# wifiboard.net
KiCad netlist of a schematic drawn in EAGLE
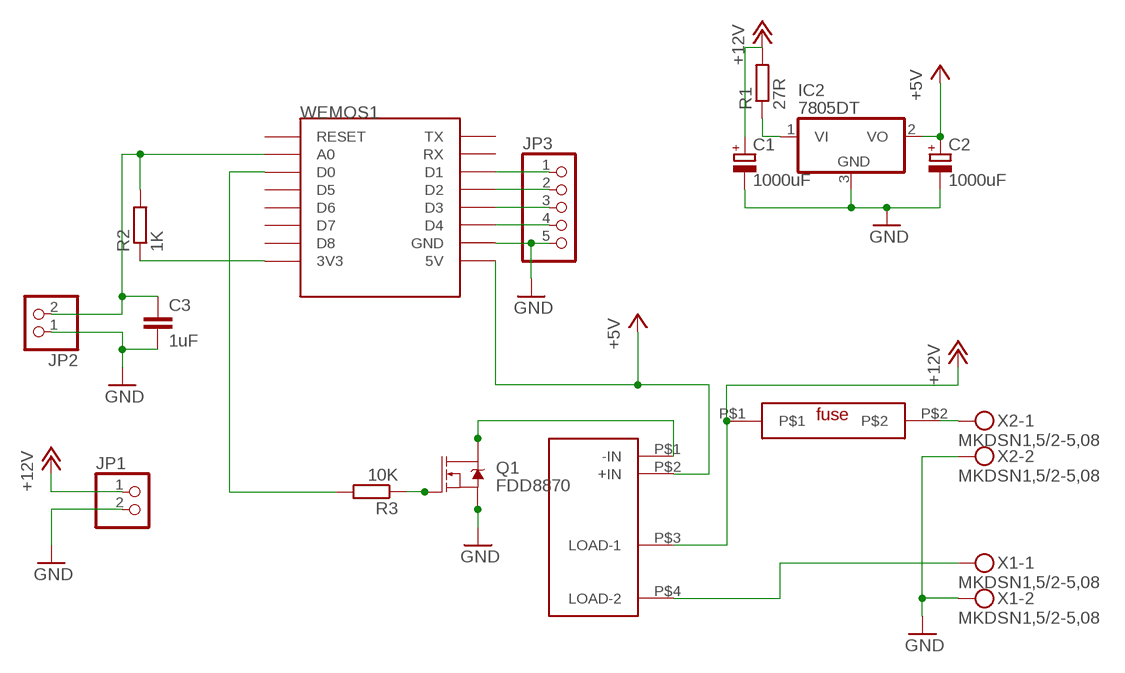
[diagram p0: schematic, sheet 1]

(export (version "E")
  (design (tool "Eeschema 10.0.6"))
  (components
    (comp (ref "C1")
      (value "1000uF")
      (footprint "eagle-import:B45181B")
      (libsource (lib "eagle-import") (part "CPOL-EUB45181B"))
    )
    (comp (ref "C2")
      (value "1000uF")
      (footprint "eagle-import:B45181B")
      (libsource (lib "eagle-import") (part "CPOL-EUB45181B"))
    )
    (comp (ref "C3")
      (value "1uF")
      (footprint "eagle-import:C0805")
      (libsource (lib "eagle-import") (part "C-EUC0805"))
    )
    (comp (ref "IC2")
      (value "7805DT")
      (footprint "eagle-import:TO252")
      (libsource (lib "eagle-import") (part "78DT05"))
    )
    (comp (ref "JP1")
      (value "PINHD-1X2")
      (footprint "eagle-import:1X02")
      (libsource (lib "eagle-import") (part "PINHD-1X2"))
    )
    (comp (ref "JP2")
      (value "PINHD-1X2")
      (footprint "eagle-import:1X02")
      (libsource (lib "eagle-import") (part "PINHD-1X2"))
    )
    (comp (ref "JP3")
      (value "PINHD-1X5")
      (footprint "eagle-import:1X05")
      (libsource (lib "eagle-import") (part "PINHD-1X5"))
    )
    (comp (ref "Q1")
      (value "FDD8870")
      (footprint "eagle-import:DPAK")
      (libsource (lib "eagle-import") (part "MOSFET-NCH-FDD8780"))
    )
    (comp (ref "R1")
      (value "27R")
      (footprint "eagle-import:0207_10")
      (libsource (lib "eagle-import") (part "R-EU_0207/10"))
    )
    (comp (ref "R2")
      (value "1K")
      (footprint "eagle-import:M0805")
      (libsource (lib "eagle-import") (part "R-EU_M0805"))
    )
    (comp (ref "R3")
      (value "10K")
      (footprint "eagle-import:M0805")
      (libsource (lib "eagle-import") (part "R-EU_M0805"))
    )
    (comp (ref "U$1")
      (value "OMRON-G6DS")
      (footprint "eagle-import:OMRON-G6DS-1A-H")
      (libsource (lib "eagle-import") (part "OMRON-G6DS"))
    )
    (comp (ref "U$2")
      (value "FUSE")
      (footprint "eagle-import:FUSE")
      (libsource (lib "eagle-import") (part "FUSE"))
    )
    (comp (ref "WEMOS1")
      (value "WEMOS-D1-MINI")
      (footprint "eagle-import:WEMOS-D1-MINI")
      (libsource (lib "eagle-import") (part "WEMOS-D1-MINI"))
    )
    (comp (ref "X1")
      (value "MKDSN1,5/2-5,08")
      (footprint "eagle-import:MKDSN1,5_2-5,08")
      (libsource (lib "eagle-import") (part "MKDSN1,5/2-5,08"))
    )
    (comp (ref "X2")
      (value "MKDSN1,5/2-5,08")
      (footprint "eagle-import:MKDSN1,5_2-5,08")
      (libsource (lib "eagle-import") (part "MKDSN1,5/2-5,08"))
    )
  )
  (nets
    (net (code "1") (name "+5V") (class "Default")
      (node (ref "C2") (pin "+") (pinfunction "+_+") (pintype "passive"))
      (node (ref "IC2") (pin "2") (pinfunction "VO_2") (pintype "passive"))
      (node (ref "U$1") (pin "P$2") (pinfunction "+IN_P$2") (pintype "input"))
      (node (ref "WEMOS1") (pin "5V") (pinfunction "5V_5V") (pintype "bidirectional"))
    )
    (net (code "2") (name "+12V") (class "Default")
      (node (ref "C1") (pin "+") (pinfunction "+_+") (pintype "passive"))
      (node (ref "JP1") (pin "1") (pinfunction "1_1") (pintype "passive"))
      (node (ref "R1") (pin "2") (pinfunction "2_2") (pintype "passive"))
      (node (ref "U$1") (pin "P$3") (pinfunction "LOAD-1_P$3") (pintype "bidirectional"))
      (node (ref "U$2") (pin "P$1") (pinfunction "P$1_P$1") (pintype "bidirectional"))
    )
    (net (code "3") (name "GND") (class "Default")
      (node (ref "C1") (pin "-") (pinfunction "-_-") (pintype "passive"))
      (node (ref "C2") (pin "-") (pinfunction "-_-") (pintype "passive"))
      (node (ref "C3") (pin "2") (pinfunction "2_2") (pintype "passive"))
      (node (ref "IC2") (pin "3") (pinfunction "GND_3") (pintype "passive"))
      (node (ref "JP1") (pin "2") (pinfunction "2_2") (pintype "passive"))
      (node (ref "JP2") (pin "1") (pinfunction "1_1") (pintype "passive"))
      (node (ref "JP3") (pin "5") (pinfunction "5_5") (pintype "passive"))
      (node (ref "Q1") (pin "3") (pinfunction "S_3") (pintype "bidirectional"))
      (node (ref "WEMOS1") (pin "GND") (pinfunction "GND_GND") (pintype "bidirectional"))
      (node (ref "X1") (pin "2") (pinfunction "KL_2") (pintype "passive"))
      (node (ref "X2") (pin "2") (pinfunction "KL_2") (pintype "passive"))
    )
    (net (code "4") (name "Net-(C3-Pad1)") (class "Default")
      (node (ref "C3") (pin "1") (pinfunction "1_1") (pintype "passive"))
      (node (ref "JP2") (pin "2") (pinfunction "2_2") (pintype "passive"))
      (node (ref "R2") (pin "2") (pinfunction "2_2") (pintype "passive"))
      (node (ref "WEMOS1") (pin "A0") (pinfunction "A0_A0") (pintype "bidirectional"))
    )
    (net (code "5") (name "Net-(IC2-VI)") (class "Default")
      (node (ref "IC2") (pin "1") (pinfunction "VI_1") (pintype "input"))
      (node (ref "R1") (pin "1") (pinfunction "1_1") (pintype "passive"))
    )
    (net (code "6") (name "Net-(JP3-Pad1)") (class "Default")
      (node (ref "JP3") (pin "1") (pinfunction "1_1") (pintype "passive"))
      (node (ref "WEMOS1") (pin "D1") (pinfunction "D1_D1") (pintype "bidirectional"))
    )
    (net (code "7") (name "Net-(JP3-Pad2)") (class "Default")
      (node (ref "JP3") (pin "2") (pinfunction "2_2") (pintype "passive"))
      (node (ref "WEMOS1") (pin "D2") (pinfunction "D2_D2") (pintype "bidirectional"))
    )
    (net (code "8") (name "Net-(JP3-Pad3)") (class "Default")
      (node (ref "JP3") (pin "3") (pinfunction "3_3") (pintype "passive"))
      (node (ref "WEMOS1") (pin "D3") (pinfunction "D3_D3") (pintype "bidirectional"))
    )
    (net (code "9") (name "Net-(JP3-Pad4)") (class "Default")
      (node (ref "JP3") (pin "4") (pinfunction "4_4") (pintype "passive"))
      (node (ref "WEMOS1") (pin "D4") (pinfunction "D4_D4") (pintype "bidirectional"))
    )
    (net (code "10") (name "Net-(Q1-D)") (class "Default")
      (node (ref "Q1") (pin "4") (pinfunction "D_4") (pintype "bidirectional"))
      (node (ref "U$1") (pin "P$1") (pinfunction "-IN_P$1") (pintype "input"))
    )
    (net (code "11") (name "Net-(Q1-G)") (class "Default")
      (node (ref "Q1") (pin "1") (pinfunction "G_1") (pintype "bidirectional"))
      (node (ref "R3") (pin "1") (pinfunction "1_1") (pintype "passive"))
    )
    (net (code "12") (name "Net-(R2-Pad1)") (class "Default")
      (node (ref "R2") (pin "1") (pinfunction "1_1") (pintype "passive"))
      (node (ref "WEMOS1") (pin "3V3") (pinfunction "3V3_3V3") (pintype "bidirectional"))
    )
    (net (code "13") (name "Net-(R3-Pad2)") (class "Default")
      (node (ref "R3") (pin "2") (pinfunction "2_2") (pintype "passive"))
      (node (ref "WEMOS1") (pin "D0") (pinfunction "D0_D0") (pintype "bidirectional"))
    )
    (net (code "14") (name "Net-(U$1-LOAD-2)") (class "Default")
      (node (ref "U$1") (pin "P$4") (pinfunction "LOAD-2_P$4") (pintype "bidirectional"))
      (node (ref "X1") (pin "1") (pinfunction "KL_1") (pintype "passive"))
    )
    (net (code "15") (name "Net-(X2A-KL)") (class "Default")
      (node (ref "U$2") (pin "P$2") (pinfunction "P$2_P$2") (pintype "bidirectional"))
      (node (ref "X2") (pin "1") (pinfunction "KL_1") (pintype "passive"))
    )
    (net (code "16") (name "unconnected-(WEMOS1-PadD5)") (class "Default")
      (node (ref "WEMOS1") (pin "D5") (pinfunction "D5_D5") (pintype "bidirectional"))
    )
    (net (code "17") (name "unconnected-(WEMOS1-PadD6)") (class "Default")
      (node (ref "WEMOS1") (pin "D6") (pinfunction "D6_D6") (pintype "bidirectional"))
    )
    (net (code "18") (name "unconnected-(WEMOS1-PadD7)") (class "Default")
      (node (ref "WEMOS1") (pin "D7") (pinfunction "D7_D7") (pintype "bidirectional"))
    )
    (net (code "19") (name "unconnected-(WEMOS1-PadD8)") (class "Default")
      (node (ref "WEMOS1") (pin "D8") (pinfunction "D8_D8") (pintype "bidirectional"))
    )
    (net (code "20") (name "unconnected-(WEMOS1-PadRESET)") (class "Default")
      (node (ref "WEMOS1") (pin "RESET") (pinfunction "RESET_RESET") (pintype "bidirectional"))
    )
    (net (code "21") (name "unconnected-(WEMOS1-PadRX)") (class "Default")
      (node (ref "WEMOS1") (pin "RX") (pinfunction "RX_RX") (pintype "bidirectional"))
    )
    (net (code "22") (name "unconnected-(WEMOS1-PadTX)") (class "Default")
      (node (ref "WEMOS1") (pin "TX") (pinfunction "TX_TX") (pintype "bidirectional"))
    )
  )
)
